# schematic_rev_1.net
KiCad netlist of a schematic drawn in EAGLE
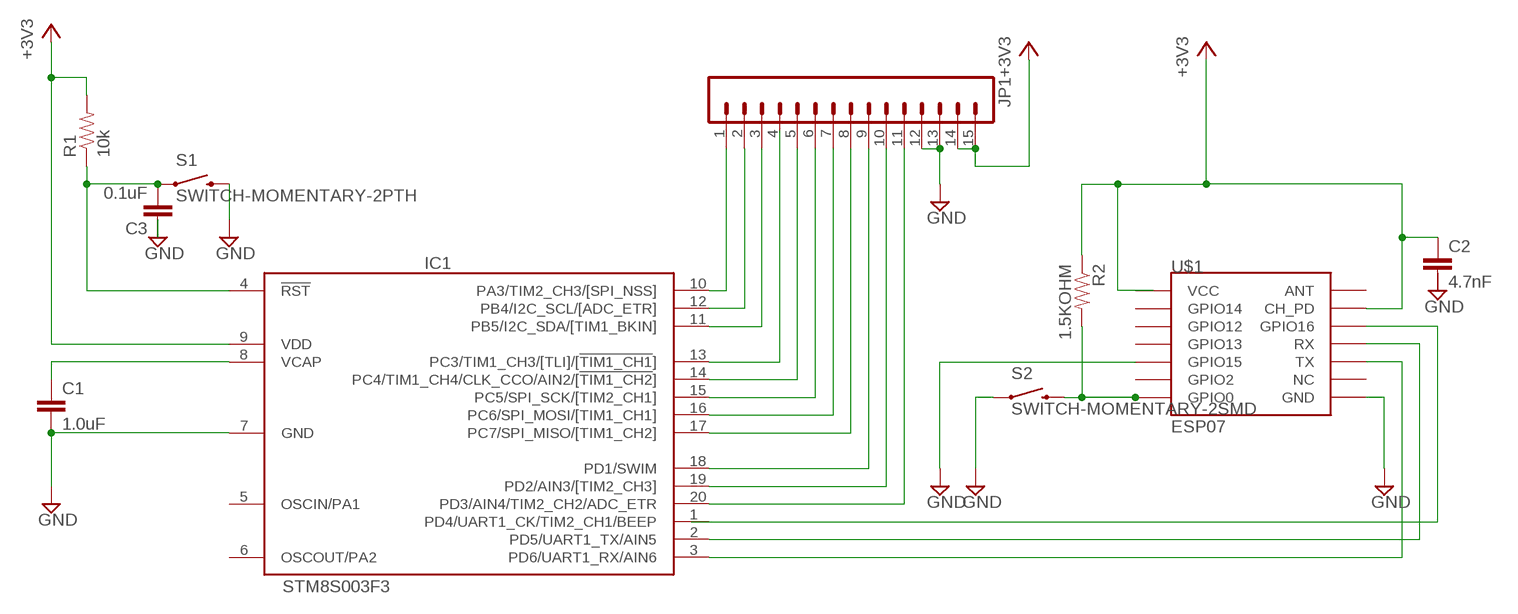
[diagram p0: schematic, sheet 1]

(export (version "E")
  (design (tool "Eeschema 10.0.6"))
  (components
    (comp (ref "C1")
      (value "1.0uF")
      (footprint "eagle-import:0402-CAP")
      (libsource (lib "eagle-import") (part "1.0UF-16V-10%(0402)"))
    )
    (comp (ref "C2")
      (value "4.7nF")
      (footprint "eagle-import:0603-CAP")
      (libsource (lib "eagle-import") (part "4.7NF-50V-10%(0603)"))
    )
    (comp (ref "C3")
      (value "0.1uF")
      (footprint "eagle-import:0402-CAP")
      (libsource (lib "eagle-import") (part "0.1UF-16V(+-10%)(0402)"))
    )
    (comp (ref "IC1")
      (value "STM8S003F3")
      (footprint "eagle-import:TSSOP20")
      (libsource (lib "eagle-import") (part "STM8S003F3"))
    )
    (comp (ref "JP1")
      (value "M15")
      (footprint "eagle-import:1X15")
      (libsource (lib "eagle-import") (part "M15"))
    )
    (comp (ref "R1")
      (value "10k")
      (footprint "eagle-import:AXIAL-0.3")
      (libsource (lib "eagle-import") (part "10KOHM-1/4W-1%(PTH)HORIZ"))
    )
    (comp (ref "R2")
      (value "1.5KOHM")
      (footprint "eagle-import:0603")
      (libsource (lib "eagle-import") (part "1.5KOHM-1/10W-1%(0603)"))
    )
    (comp (ref "S1")
      (value "SWITCH-MOMENTARY-2PTH")
      (footprint "eagle-import:TACTILE-PTH")
      (libsource (lib "eagle-import") (part "SWITCH-MOMENTARY-2PTH"))
    )
    (comp (ref "S2")
      (value "SWITCH-MOMENTARY-2SMD")
      (footprint "eagle-import:TACTILE-SWITCH-SMD")
      (libsource (lib "eagle-import") (part "SWITCH-MOMENTARY-2SMD"))
    )
    (comp (ref "U$1")
      (value "ESP07")
      (footprint "eagle-import:ESP07")
      (libsource (lib "eagle-import") (part "ESP07"))
    )
  )
  (nets
    (net (code "1") (name "+3V3") (class "Default")
      (node (ref "C2") (pin "1") (pinfunction "1_1") (pintype "passive"))
      (node (ref "IC1") (pin "9") (pinfunction "VDD_9") (pintype "power_in"))
      (node (ref "JP1") (pin "14") (pinfunction "14_14") (pintype "passive"))
      (node (ref "JP1") (pin "15") (pinfunction "15_15") (pintype "passive"))
      (node (ref "R1") (pin "P$2") (pinfunction "2_P$2") (pintype "passive"))
      (node (ref "R2") (pin "1") (pinfunction "1_1") (pintype "passive"))
      (node (ref "U$1") (pin "CH_PD") (pinfunction "CH_PD_CH_PD") (pintype "bidirectional"))
    )
    (net (code "2") (name "GND") (class "Default")
      (node (ref "C1") (pin "2") (pinfunction "2_2") (pintype "passive"))
      (node (ref "C3") (pin "1") (pinfunction "1_1") (pintype "passive"))
      (node (ref "IC1") (pin "7") (pinfunction "GND_7") (pintype "power_in"))
      (node (ref "JP1") (pin "12") (pinfunction "12_12") (pintype "passive"))
      (node (ref "JP1") (pin "13") (pinfunction "13_13") (pintype "passive"))
      (node (ref "S1") (pin "3") (pinfunction "2_3") (pintype "passive"))
      (node (ref "S2") (pin "1") (pinfunction "1_1") (pintype "passive"))
      (node (ref "U$1") (pin "GND") (pinfunction "GND_GND") (pintype "bidirectional"))
      (node (ref "U$1") (pin "GPIO15") (pinfunction "GPIO15_GPIO15") (pintype "bidirectional"))
    )
    (net (code "3") (name "Net-(IC1-PA3{slash}TIM2_CH3{slash}[SPI_NSS])") (class "Default")
      (node (ref "IC1") (pin "10") (pinfunction "PA3/TIM2_CH3/[SPI_NSS]_10") (pintype "bidirectional"))
      (node (ref "JP1") (pin "1") (pinfunction "1_1") (pintype "passive"))
    )
    (net (code "4") (name "Net-(IC1-PB4{slash}I2C_SCL{slash}[ADC_ETR])") (class "Default")
      (node (ref "IC1") (pin "12") (pinfunction "PB4/I2C_SCL/[ADC_ETR]_12") (pintype "bidirectional"))
      (node (ref "JP1") (pin "2") (pinfunction "2_2") (pintype "passive"))
    )
    (net (code "5") (name "Net-(IC1-PB5{slash}I2C_SDA{slash}[TIM1_BKIN])") (class "Default")
      (node (ref "IC1") (pin "11") (pinfunction "PB5/I2C_SDA/[TIM1_BKIN]_11") (pintype "bidirectional"))
      (node (ref "JP1") (pin "3") (pinfunction "3_3") (pintype "passive"))
    )
    (net (code "6") (name "Net-(IC1-PC3{slash}TIM1_CH3{slash}[TLI]{slash}[~{TIM1_CH1}])") (class "Default")
      (node (ref "IC1") (pin "13") (pinfunction "PC3/TIM1_CH3/[TLI]/[~{TIM1_CH1}]_13") (pintype "bidirectional"))
      (node (ref "JP1") (pin "4") (pinfunction "4_4") (pintype "passive"))
    )
    (net (code "7") (name "Net-(IC1-PC4{slash}TIM1_CH4{slash}CLK_CCO{slash}AIN2{slash}[~{TIM1_CH2}])") (class "Default")
      (node (ref "IC1") (pin "14") (pinfunction "PC4/TIM1_CH4/CLK_CCO/AIN2/[~{TIM1_CH2}]_14") (pintype "bidirectional"))
      (node (ref "JP1") (pin "5") (pinfunction "5_5") (pintype "passive"))
    )
    (net (code "8") (name "Net-(IC1-PC5{slash}SPI_SCK{slash}[TIM2_CH1])") (class "Default")
      (node (ref "IC1") (pin "15") (pinfunction "PC5/SPI_SCK/[TIM2_CH1]_15") (pintype "bidirectional"))
      (node (ref "JP1") (pin "6") (pinfunction "6_6") (pintype "passive"))
    )
    (net (code "9") (name "Net-(IC1-PC6{slash}SPI_MOSI{slash}[TIM1_CH1])") (class "Default")
      (node (ref "IC1") (pin "16") (pinfunction "PC6/SPI_MOSI/[TIM1_CH1]_16") (pintype "bidirectional"))
      (node (ref "JP1") (pin "7") (pinfunction "7_7") (pintype "passive"))
    )
    (net (code "10") (name "Net-(IC1-PC7{slash}SPI_MISO{slash}[TIM1_CH2])") (class "Default")
      (node (ref "IC1") (pin "17") (pinfunction "PC7/SPI_MISO/[TIM1_CH2]_17") (pintype "bidirectional"))
      (node (ref "JP1") (pin "8") (pinfunction "8_8") (pintype "passive"))
    )
    (net (code "11") (name "Net-(IC1-PD1{slash}SWIM)") (class "Default")
      (node (ref "IC1") (pin "18") (pinfunction "PD1/SWIM_18") (pintype "bidirectional"))
      (node (ref "JP1") (pin "9") (pinfunction "9_9") (pintype "passive"))
    )
    (net (code "12") (name "Net-(IC1-PD2{slash}AIN3{slash}[TIM2_CH3])") (class "Default")
      (node (ref "IC1") (pin "19") (pinfunction "PD2/AIN3/[TIM2_CH3]_19") (pintype "bidirectional"))
      (node (ref "JP1") (pin "10") (pinfunction "10_10") (pintype "passive"))
    )
    (net (code "13") (name "Net-(IC1-PD3{slash}AIN4{slash}TIM2_CH2{slash}ADC_ETR)") (class "Default")
      (node (ref "IC1") (pin "20") (pinfunction "PD3/AIN4/TIM2_CH2/ADC_ETR_20") (pintype "bidirectional"))
      (node (ref "JP1") (pin "11") (pinfunction "11_11") (pintype "passive"))
    )
    (net (code "14") (name "Net-(IC1-PD5{slash}UART1_TX{slash}AIN5)") (class "Default")
      (node (ref "IC1") (pin "2") (pinfunction "PD5/UART1_TX/AIN5_2") (pintype "bidirectional"))
      (node (ref "U$1") (pin "RX") (pinfunction "RX_RX") (pintype "bidirectional"))
    )
    (net (code "15") (name "Net-(IC1-PD6{slash}UART1_RX{slash}AIN6)") (class "Default")
      (node (ref "IC1") (pin "3") (pinfunction "PD6/UART1_RX/AIN6_3") (pintype "bidirectional"))
      (node (ref "U$1") (pin "TX") (pinfunction "TX_TX") (pintype "bidirectional"))
    )
    (net (code "16") (name "Net-(IC1-VCAP)") (class "Default")
      (node (ref "C1") (pin "1") (pinfunction "1_1") (pintype "passive"))
      (node (ref "IC1") (pin "8") (pinfunction "VCAP_8") (pintype "power_in"))
    )
    (net (code "17") (name "Net-(IC1-~{RST})") (class "Default")
      (node (ref "C3") (pin "2") (pinfunction "2_2") (pintype "passive"))
      (node (ref "IC1") (pin "4") (pinfunction "~{RST}_4") (pintype "input"))
      (node (ref "R1") (pin "P$1") (pinfunction "1_P$1") (pintype "passive"))
      (node (ref "S1") (pin "1") (pinfunction "1_1") (pintype "passive"))
    )
    (net (code "18") (name "Net-(S2-2)") (class "Default")
      (node (ref "R2") (pin "2") (pinfunction "2_2") (pintype "passive"))
      (node (ref "S2") (pin "3") (pinfunction "2_3") (pintype "passive"))
      (node (ref "U$1") (pin "GPIO0") (pinfunction "GPIO0_GPIO0") (pintype "bidirectional"))
    )
    (net (code "19") (name "unconnected-(C2-Pad2)") (class "Default")
      (node (ref "C2") (pin "2") (pinfunction "2_2") (pintype "passive"))
    )
    (net (code "20") (name "unconnected-(IC1-OSCIN{slash}PA1-Pad5)") (class "Default")
      (node (ref "IC1") (pin "5") (pinfunction "OSCIN/PA1_5") (pintype "bidirectional"))
    )
    (net (code "21") (name "unconnected-(IC1-OSCOUT{slash}PA2-Pad6)") (class "Default")
      (node (ref "IC1") (pin "6") (pinfunction "OSCOUT/PA2_6") (pintype "bidirectional"))
    )
    (net (code "22") (name "unconnected-(IC1-PD4{slash}UART1_CK{slash}TIM2_CH1{slash}BEEP-Pad1)") (class "Default")
      (node (ref "IC1") (pin "1") (pinfunction "PD4/UART1_CK/TIM2_CH1/BEEP_1") (pintype "bidirectional"))
    )
    (net (code "23") (name "unconnected-(U$1-PadANT)") (class "Default")
      (node (ref "U$1") (pin "ANT") (pinfunction "ANT_ANT") (pintype "bidirectional"))
    )
    (net (code "24") (name "unconnected-(U$1-PadGPIO2)") (class "Default")
      (node (ref "U$1") (pin "GPIO2") (pinfunction "GPIO2_GPIO2") (pintype "bidirectional"))
    )
    (net (code "25") (name "unconnected-(U$1-PadGPIO12)") (class "Default")
      (node (ref "U$1") (pin "GPIO12") (pinfunction "GPIO12_GPIO12") (pintype "bidirectional"))
    )
    (net (code "26") (name "unconnected-(U$1-PadGPIO13)") (class "Default")
      (node (ref "U$1") (pin "GPIO13") (pinfunction "GPIO13_GPIO13") (pintype "bidirectional"))
    )
    (net (code "27") (name "unconnected-(U$1-PadGPIO14)") (class "Default")
      (node (ref "U$1") (pin "GPIO14") (pinfunction "GPIO14_GPIO14") (pintype "bidirectional"))
    )
    (net (code "28") (name "unconnected-(U$1-PadGPIO16)") (class "Default")
      (node (ref "U$1") (pin "GPIO16") (pinfunction "GPIO16_GPIO16") (pintype "bidirectional"))
    )
    (net (code "29") (name "unconnected-(U$1-PadNC)") (class "Default")
      (node (ref "U$1") (pin "NC") (pinfunction "NC_NC") (pintype "bidirectional"))
    )
    (net (code "30") (name "unconnected-(U$1-PadVCC)") (class "Default")
      (node (ref "U$1") (pin "VCC") (pinfunction "VCC_VCC") (pintype "bidirectional"))
    )
  )
)
